# raspi.net
KiCad netlist of a schematic drawn in EAGLE
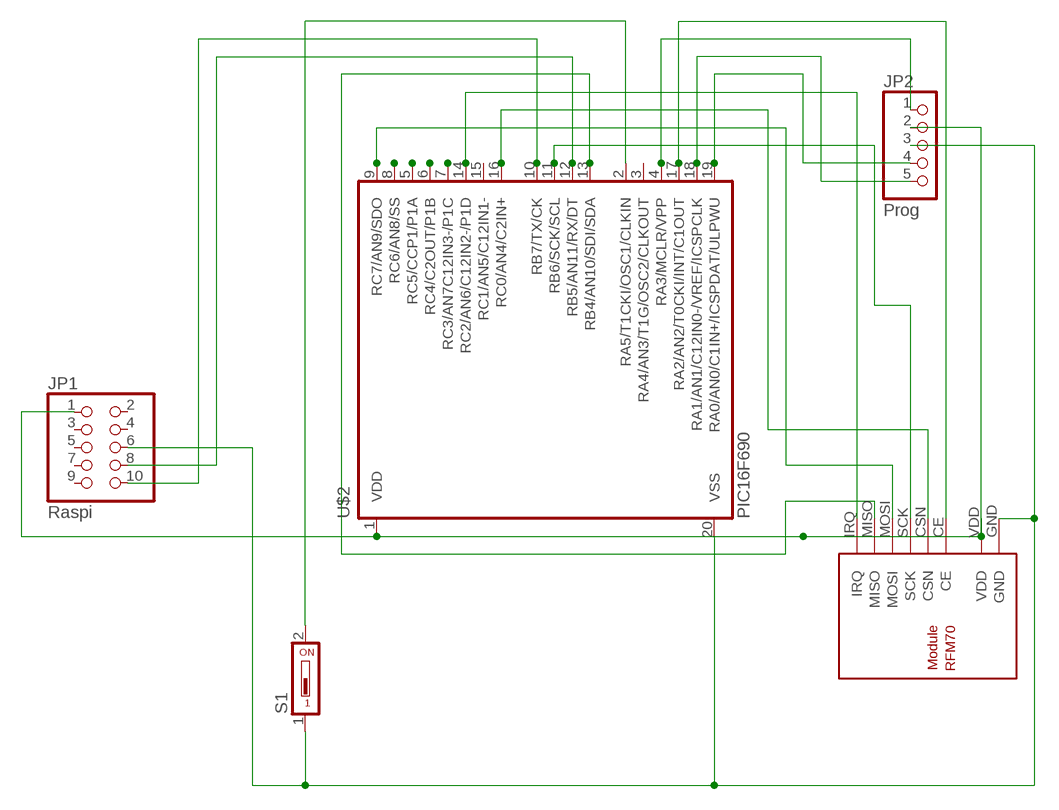
[diagram p0: schematic, sheet 1]

(export (version "E")
  (design (tool "Eeschema 10.0.6"))
  (components
    (comp (ref "JP1")
      (value "Raspi")
      (footprint "eagle-import:2X05")
      (libsource (lib "eagle-import") (part "PINHD-2X5"))
    )
    (comp (ref "JP2")
      (value "Prog")
      (footprint "eagle-import:1X05")
      (libsource (lib "eagle-import") (part "PINHD-1X5"))
    )
    (comp (ref "S1")
      (value "SD4-01")
      (footprint "eagle-import:SD4-01")
      (libsource (lib "eagle-import") (part "SD4-01"))
    )
    (comp (ref "U$1")
      (value "RFM70")
      (footprint "eagle-import:RFM70")
      (libsource (lib "eagle-import") (part "RFM70"))
    )
    (comp (ref "U$2")
      (value "PIC16F690")
      (footprint "eagle-import:SSOP20")
      (libsource (lib "eagle-import") (part "PIC16F690"))
    )
  )
  (nets
    (net (code "1") (name "Net-(U$2-RA0{slash}AN0{slash}C1IN+{slash}ICSPDAT{slash}ULPWU)") (class "Default")
      (node (ref "JP2") (pin "4") (pinfunction "4_4") (pintype "passive"))
      (node (ref "U$2") (pin "19") (pinfunction "RA0/AN0/C1IN+/ICSPDAT/ULPWU_19") (pintype "bidirectional"))
    )
    (net (code "2") (name "Net-(U$2-RA1{slash}AN1{slash}C12IN0-{slash}VREF{slash}ICSPCLK)") (class "Default")
      (node (ref "JP2") (pin "5") (pinfunction "5_5") (pintype "passive"))
      (node (ref "U$2") (pin "18") (pinfunction "RA1/AN1/C12IN0-/VREF/ICSPCLK_18") (pintype "bidirectional"))
    )
    (net (code "3") (name "Net-(U$2-RA2{slash}AN2{slash}T0CKI{slash}INT{slash}C1OUT)") (class "Default")
      (node (ref "U$1") (pin "CE") (pinfunction "CE_CE") (pintype "bidirectional"))
      (node (ref "U$2") (pin "17") (pinfunction "RA2/AN2/T0CKI/INT/C1OUT_17") (pintype "bidirectional"))
    )
    (net (code "4") (name "Net-(U$2-RA3{slash}MCLR{slash}VPP)") (class "Default")
      (node (ref "JP2") (pin "1") (pinfunction "1_1") (pintype "passive"))
      (node (ref "U$2") (pin "4") (pinfunction "RA3/MCLR/VPP_4") (pintype "bidirectional"))
    )
    (net (code "5") (name "Net-(U$2-RA5{slash}T1CKI{slash}OSC1{slash}CLKIN)") (class "Default")
      (node (ref "S1") (pin "2") (pinfunction "2_2") (pintype "passive"))
      (node (ref "U$2") (pin "2") (pinfunction "RA5/T1CKI/OSC1/CLKIN_2") (pintype "bidirectional"))
    )
    (net (code "6") (name "Net-(U$2-RB4{slash}AN10{slash}SDI{slash}SDA)") (class "Default")
      (node (ref "U$1") (pin "MISO") (pinfunction "MISO_MISO") (pintype "bidirectional"))
      (node (ref "U$2") (pin "13") (pinfunction "RB4/AN10/SDI/SDA_13") (pintype "bidirectional"))
    )
    (net (code "7") (name "Net-(U$2-RB5{slash}AN11{slash}RX{slash}DT)") (class "Default")
      (node (ref "JP1") (pin "8") (pinfunction "8_8") (pintype "passive"))
      (node (ref "U$2") (pin "12") (pinfunction "RB5/AN11/RX/DT_12") (pintype "bidirectional"))
    )
    (net (code "8") (name "Net-(U$2-RB6{slash}SCK{slash}SCL)") (class "Default")
      (node (ref "U$1") (pin "SCK") (pinfunction "SCK_SCK") (pintype "bidirectional"))
      (node (ref "U$2") (pin "11") (pinfunction "RB6/SCK/SCL_11") (pintype "bidirectional"))
    )
    (net (code "9") (name "Net-(U$2-RB7{slash}TX{slash}CK)") (class "Default")
      (node (ref "JP1") (pin "10") (pinfunction "10_10") (pintype "passive"))
      (node (ref "U$2") (pin "10") (pinfunction "RB7/TX/CK_10") (pintype "bidirectional"))
    )
    (net (code "10") (name "Net-(U$2-RC0{slash}AN4{slash}C2IN+)") (class "Default")
      (node (ref "U$1") (pin "CSN") (pinfunction "CSN_CSN") (pintype "bidirectional"))
      (node (ref "U$2") (pin "16") (pinfunction "RC0/AN4/C2IN+_16") (pintype "bidirectional"))
    )
    (net (code "11") (name "Net-(U$2-RC2{slash}AN6{slash}C12IN2-{slash}P1D)") (class "Default")
      (node (ref "U$1") (pin "IRQ") (pinfunction "IRQ_IRQ") (pintype "bidirectional"))
      (node (ref "U$2") (pin "14") (pinfunction "RC2/AN6/C12IN2-/P1D_14") (pintype "bidirectional"))
    )
    (net (code "12") (name "Net-(U$2-RC7{slash}AN9{slash}SDO)") (class "Default")
      (node (ref "U$1") (pin "MOSI") (pinfunction "MOSI_MOSI") (pintype "bidirectional"))
      (node (ref "U$2") (pin "9") (pinfunction "RC7/AN9/SDO_9") (pintype "bidirectional"))
    )
    (net (code "13") (name "Net-(U$2-VDD)") (class "Default")
      (node (ref "JP1") (pin "1") (pinfunction "1_1") (pintype "passive"))
      (node (ref "JP2") (pin "2") (pinfunction "2_2") (pintype "passive"))
      (node (ref "U$1") (pin "VDD") (pinfunction "VDD_VDD") (pintype "power_in"))
      (node (ref "U$2") (pin "1") (pinfunction "VDD_1") (pintype "power_in"))
    )
    (net (code "14") (name "Net-(U$2-VSS)") (class "Default")
      (node (ref "JP1") (pin "6") (pinfunction "6_6") (pintype "passive"))
      (node (ref "JP2") (pin "3") (pinfunction "3_3") (pintype "passive"))
      (node (ref "S1") (pin "1") (pinfunction "1_1") (pintype "passive"))
      (node (ref "U$1") (pin "GND") (pinfunction "GND_GND") (pintype "power_in"))
      (node (ref "U$2") (pin "20") (pinfunction "VSS_20") (pintype "power_in"))
    )
    (net (code "15") (name "unconnected-(JP1-Pad2)") (class "Default")
      (node (ref "JP1") (pin "2") (pinfunction "2_2") (pintype "passive"))
    )
    (net (code "16") (name "unconnected-(JP1-Pad3)") (class "Default")
      (node (ref "JP1") (pin "3") (pinfunction "3_3") (pintype "passive"))
    )
    (net (code "17") (name "unconnected-(JP1-Pad4)") (class "Default")
      (node (ref "JP1") (pin "4") (pinfunction "4_4") (pintype "passive"))
    )
    (net (code "18") (name "unconnected-(JP1-Pad5)") (class "Default")
      (node (ref "JP1") (pin "5") (pinfunction "5_5") (pintype "passive"))
    )
    (net (code "19") (name "unconnected-(JP1-Pad7)") (class "Default")
      (node (ref "JP1") (pin "7") (pinfunction "7_7") (pintype "passive"))
    )
    (net (code "20") (name "unconnected-(JP1-Pad9)") (class "Default")
      (node (ref "JP1") (pin "9") (pinfunction "9_9") (pintype "passive"))
    )
    (net (code "21") (name "unconnected-(U$2-RA4{slash}AN3{slash}T1G{slash}OSC2{slash}CLKOUT-Pad3)") (class "Default")
      (node (ref "U$2") (pin "3") (pinfunction "RA4/AN3/T1G/OSC2/CLKOUT_3") (pintype "bidirectional"))
    )
    (net (code "22") (name "unconnected-(U$2-RC1{slash}AN5{slash}C12IN1--Pad15)") (class "Default")
      (node (ref "U$2") (pin "15") (pinfunction "RC1/AN5/C12IN1-_15") (pintype "bidirectional"))
    )
    (net (code "23") (name "unconnected-(U$2-RC3{slash}AN7C12IN3-{slash}P1C-Pad7)") (class "Default")
      (node (ref "U$2") (pin "7") (pinfunction "RC3/AN7C12IN3-/P1C_7") (pintype "bidirectional"))
    )
    (net (code "24") (name "unconnected-(U$2-RC4{slash}C2OUT{slash}P1B-Pad6)") (class "Default")
      (node (ref "U$2") (pin "6") (pinfunction "RC4/C2OUT/P1B_6") (pintype "bidirectional"))
    )
    (net (code "25") (name "unconnected-(U$2-RC5{slash}CCP1{slash}P1A-Pad5)") (class "Default")
      (node (ref "U$2") (pin "5") (pinfunction "RC5/CCP1/P1A_5") (pintype "bidirectional"))
    )
    (net (code "26") (name "unconnected-(U$2-RC6{slash}AN8{slash}SS-Pad8)") (class "Default")
      (node (ref "U$2") (pin "8") (pinfunction "RC6/AN8/SS_8") (pintype "bidirectional"))
    )
  )
)
